# design.net
KiCad netlist of a schematic drawn in Altium Designer
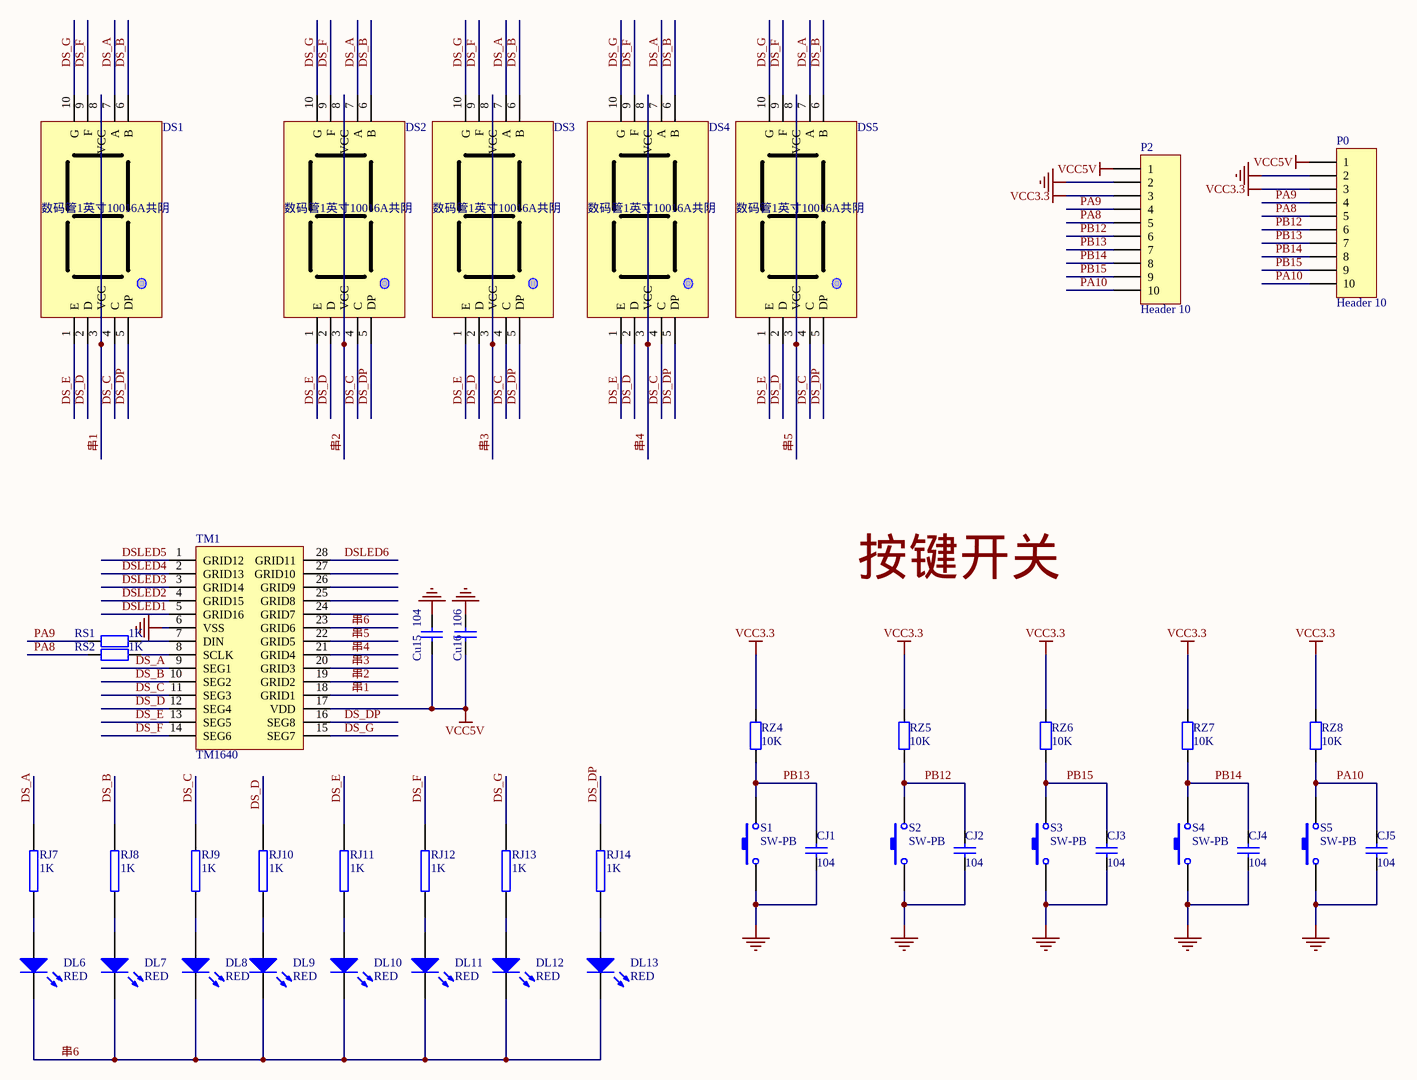
[diagram p0: 铁壳显示板.SchDoc]

(export (version "E")
  (design (tool "Eeschema 10.0.6"))
  (components
    (comp (ref "CJ1")
      (value "104")
      (footprint "0603-1")
      (description "Capacitor")
      (fields (field (name "PUBLISHER") "Altium Limited"))
      (libsource (lib "原理图库") (part "104"))
    )
    (comp (ref "CJ2")
      (value "104")
      (footprint "0603-1")
      (description "Capacitor")
      (fields (field (name "PUBLISHER") "Altium Limited"))
      (libsource (lib "原理图库") (part "104"))
    )
    (comp (ref "CJ3")
      (value "104")
      (footprint "0603-1")
      (description "Capacitor")
      (fields (field (name "PUBLISHER") "Altium Limited"))
      (libsource (lib "原理图库") (part "104"))
    )
    (comp (ref "CJ4")
      (value "104")
      (footprint "0603-1")
      (description "Capacitor")
      (fields (field (name "PUBLISHER") "Altium Limited"))
      (libsource (lib "原理图库") (part "104"))
    )
    (comp (ref "CJ5")
      (value "104")
      (footprint "0603-1")
      (description "Capacitor")
      (fields (field (name "PUBLISHER") "Altium Limited"))
      (libsource (lib "原理图库") (part "104"))
    )
    (comp (ref "Cu15")
      (value "104")
      (footprint "0603-1")
      (description "Capacitor")
      (libsource (lib "*") (part "Cap"))
    )
    (comp (ref "Cu16")
      (value "106")
      (footprint "0805")
      (description "Capacitor")
      (libsource (lib "*") (part "Cap"))
    )
    (comp (ref "DL6")
      (value "RED")
      (footprint "HDR1X2")
      (description "Typical RED GaAs LED")
      (fields (field (name "PUBLISHER") "Altium Limited"))
      (libsource (lib "原理图库") (part "LED1"))
    )
    (comp (ref "DL7")
      (value "RED")
      (footprint "HDR1X2")
      (description "Typical RED GaAs LED")
      (fields (field (name "PUBLISHER") "Altium Limited"))
      (libsource (lib "原理图库") (part "LED1"))
    )
    (comp (ref "DL8")
      (value "RED")
      (footprint "HDR1X2")
      (description "Typical RED GaAs LED")
      (fields (field (name "PUBLISHER") "Altium Limited"))
      (libsource (lib "原理图库") (part "LED1"))
    )
    (comp (ref "DL9")
      (value "RED")
      (footprint "HDR1X2")
      (description "Typical RED GaAs LED")
      (fields (field (name "PUBLISHER") "Altium Limited"))
      (libsource (lib "原理图库") (part "LED1"))
    )
    (comp (ref "DL10")
      (value "RED")
      (footprint "HDR1X2")
      (description "Typical RED GaAs LED")
      (fields (field (name "PUBLISHER") "Altium Limited"))
      (libsource (lib "原理图库") (part "LED1"))
    )
    (comp (ref "DL11")
      (value "RED")
      (footprint "HDR1X2")
      (description "Typical RED GaAs LED")
      (fields (field (name "PUBLISHER") "Altium Limited"))
      (libsource (lib "原理图库") (part "LED1"))
    )
    (comp (ref "DL12")
      (value "RED")
      (footprint "HDR1X2")
      (description "Typical RED GaAs LED")
      (fields (field (name "PUBLISHER") "Altium Limited"))
      (libsource (lib "原理图库") (part "LED1"))
    )
    (comp (ref "DL13")
      (value "RED")
      (footprint "HDR1X2")
      (description "Typical RED GaAs LED")
      (fields (field (name "PUBLISHER") "Altium Limited"))
      (libsource (lib "原理图库") (part "LED1"))
    )
    (comp (ref "DS1")
      (value "数码管1英寸10016A共阴")
      (footprint "1英寸1位数码管")
      (libsource (lib "SCH原理图库") (part "数码管1英寸"))
    )
    (comp (ref "DS2")
      (value "数码管1英寸10016A共阴")
      (footprint "1英寸1位数码管")
      (libsource (lib "SCH原理图库") (part "数码管1英寸"))
    )
    (comp (ref "DS3")
      (value "数码管1英寸10016A共阴")
      (footprint "1英寸1位数码管")
      (libsource (lib "SCH原理图库") (part "数码管1英寸"))
    )
    (comp (ref "DS4")
      (value "数码管1英寸10016A共阴")
      (footprint "1英寸1位数码管")
      (libsource (lib "SCH原理图库") (part "数码管1英寸"))
    )
    (comp (ref "DS5")
      (value "数码管1英寸10016A共阴")
      (footprint "1英寸1位数码管")
      (libsource (lib "SCH原理图库") (part "数码管1英寸"))
    )
    (comp (ref "P0")
      (value "Header 10")
      (footprint "HDR1X10")
      (description "Header, 10-Pin")
      (fields (field (name "PUBLISHER") "Altium Limited"))
      (libsource (lib "SCH原理图库") (part "Header 10"))
    )
    (comp (ref "P2")
      (value "Header 10")
      (footprint "HDR1X10")
      (description "Header, 10-Pin")
      (fields (field (name "PUBLISHER") "Altium Limited"))
      (libsource (lib "SCH原理图库") (part "Header 10"))
    )
    (comp (ref "RJ7") (value "1K") (footprint "0603-1") (libsource (lib "*") (part "RES2")))
    (comp (ref "RJ8") (value "1K") (footprint "0603-1") (libsource (lib "*") (part "RES2")))
    (comp (ref "RJ9") (value "1K") (footprint "0603-1") (libsource (lib "*") (part "RES2")))
    (comp (ref "RJ10") (value "1K") (footprint "0603-1") (libsource (lib "*") (part "RES2")))
    (comp (ref "RJ11") (value "1K") (footprint "0603-1") (libsource (lib "*") (part "RES2")))
    (comp (ref "RJ12") (value "1K") (footprint "0603-1") (libsource (lib "*") (part "RES2")))
    (comp (ref "RJ13") (value "1K") (footprint "0603-1") (libsource (lib "*") (part "RES2")))
    (comp (ref "RJ14") (value "1K") (footprint "0603-1") (libsource (lib "*") (part "RES2")))
    (comp (ref "RS1")
      (value "1K")
      (footprint "0603-1")
      (description "Resistor")
      (libsource (lib "") (part "Res2_1"))
    )
    (comp (ref "RS2")
      (value "1K")
      (footprint "0603-1")
      (description "Resistor")
      (libsource (lib "") (part "Res2_1"))
    )
    (comp (ref "RZ4")
      (value "10K")
      (footprint "0603-1")
      (description "Resistor")
      (fields (field (name "PUBLISHER") "Altium Limited"))
      (libsource (lib "Miscellaneous Devices") (part "Res2"))
    )
    (comp (ref "RZ5")
      (value "10K")
      (footprint "0603-1")
      (description "Resistor")
      (fields (field (name "PUBLISHER") "Altium Limited"))
      (libsource (lib "Miscellaneous Devices") (part "Res2"))
    )
    (comp (ref "RZ6")
      (value "10K")
      (footprint "0603-1")
      (description "Resistor")
      (fields (field (name "PUBLISHER") "Altium Limited"))
      (libsource (lib "Miscellaneous Devices") (part "Res2"))
    )
    (comp (ref "RZ7")
      (value "10K")
      (footprint "0603-1")
      (description "Resistor")
      (fields (field (name "PUBLISHER") "Altium Limited"))
      (libsource (lib "Miscellaneous Devices") (part "Res2"))
    )
    (comp (ref "RZ8")
      (value "10K")
      (footprint "0603-1")
      (description "Resistor")
      (fields (field (name "PUBLISHER") "Altium Limited"))
      (libsource (lib "Miscellaneous Devices") (part "Res2"))
    )
    (comp (ref "S1")
      (value "SW-PB")
      (footprint "SW_2 - SMT")
      (description "Switch")
      (fields (field (name "PUBLISHER") "Altium Limited"))
      (libsource (lib "SCH原理图库") (part "SW-PB"))
    )
    (comp (ref "S2")
      (value "SW-PB")
      (footprint "SW_2 - SMT")
      (description "Switch")
      (fields (field (name "PUBLISHER") "Altium Limited"))
      (libsource (lib "SCH原理图库") (part "SW-PB"))
    )
    (comp (ref "S3")
      (value "SW-PB")
      (footprint "SW_2 - SMT")
      (description "Switch")
      (fields (field (name "PUBLISHER") "Altium Limited"))
      (libsource (lib "SCH原理图库") (part "SW-PB"))
    )
    (comp (ref "S4")
      (value "SW-PB")
      (footprint "SW_2 - SMT")
      (description "Switch")
      (fields (field (name "PUBLISHER") "Altium Limited"))
      (libsource (lib "SCH原理图库") (part "SW-PB"))
    )
    (comp (ref "S5")
      (value "SW-PB")
      (footprint "SW_2 - SMT")
      (description "Switch")
      (fields (field (name "PUBLISHER") "Altium Limited"))
      (libsource (lib "SCH原理图库") (part "SW-PB"))
    )
    (comp (ref "TM1") (value "TM1640") (footprint "TM1640") (libsource (lib "SCH原理图库") (part "TM1640")))
  )
  (nets
    (net (code "1") (name "/DSLED1") (class "Default")
      (node (ref "TM1") (pin "5") (pinfunction "GRID16_5") (pintype "passive"))
    )
    (net (code "2") (name "/DSLED2") (class "Default")
      (node (ref "TM1") (pin "4") (pinfunction "GRID15_4") (pintype "passive"))
    )
    (net (code "3") (name "/DSLED3") (class "Default")
      (node (ref "TM1") (pin "3") (pinfunction "GRID14_3") (pintype "passive"))
    )
    (net (code "4") (name "/DSLED4") (class "Default")
      (node (ref "TM1") (pin "2") (pinfunction "GRID13_2") (pintype "passive"))
    )
    (net (code "5") (name "/DSLED5") (class "Default")
      (node (ref "TM1") (pin "1") (pinfunction "GRID12_1") (pintype "passive"))
    )
    (net (code "6") (name "/DSLED6") (class "Default")
      (node (ref "TM1") (pin "28") (pinfunction "GRID11_28") (pintype "passive"))
    )
    (net (code "7") (name "/DS_A") (class "Default")
      (node (ref "DS1") (pin "7") (pinfunction "A_7") (pintype "passive"))
      (node (ref "DS2") (pin "7") (pinfunction "A_7") (pintype "passive"))
      (node (ref "DS3") (pin "7") (pinfunction "A_7") (pintype "passive"))
      (node (ref "DS4") (pin "7") (pinfunction "A_7") (pintype "passive"))
      (node (ref "DS5") (pin "7") (pinfunction "A_7") (pintype "passive"))
      (node (ref "RJ7") (pin "1") (pinfunction "1_1") (pintype "passive"))
      (node (ref "TM1") (pin "9") (pinfunction "SEG1_9") (pintype "passive"))
    )
    (net (code "8") (name "/DS_B") (class "Default")
      (node (ref "DS1") (pin "6") (pinfunction "B_6") (pintype "passive"))
      (node (ref "DS2") (pin "6") (pinfunction "B_6") (pintype "passive"))
      (node (ref "DS3") (pin "6") (pinfunction "B_6") (pintype "passive"))
      (node (ref "DS4") (pin "6") (pinfunction "B_6") (pintype "passive"))
      (node (ref "DS5") (pin "6") (pinfunction "B_6") (pintype "passive"))
      (node (ref "RJ8") (pin "1") (pinfunction "1_1") (pintype "passive"))
      (node (ref "TM1") (pin "10") (pinfunction "SEG2_10") (pintype "passive"))
    )
    (net (code "9") (name "/DS_C") (class "Default")
      (node (ref "DS1") (pin "4") (pinfunction "C_4") (pintype "passive"))
      (node (ref "DS2") (pin "4") (pinfunction "C_4") (pintype "passive"))
      (node (ref "DS3") (pin "4") (pinfunction "C_4") (pintype "passive"))
      (node (ref "DS4") (pin "4") (pinfunction "C_4") (pintype "passive"))
      (node (ref "DS5") (pin "4") (pinfunction "C_4") (pintype "passive"))
      (node (ref "RJ9") (pin "1") (pinfunction "1_1") (pintype "passive"))
      (node (ref "TM1") (pin "11") (pinfunction "SEG3_11") (pintype "passive"))
    )
    (net (code "10") (name "/DS_D") (class "Default")
      (node (ref "DS1") (pin "2") (pinfunction "D_2") (pintype "passive"))
      (node (ref "DS2") (pin "2") (pinfunction "D_2") (pintype "passive"))
      (node (ref "DS3") (pin "2") (pinfunction "D_2") (pintype "passive"))
      (node (ref "DS4") (pin "2") (pinfunction "D_2") (pintype "passive"))
      (node (ref "DS5") (pin "2") (pinfunction "D_2") (pintype "passive"))
      (node (ref "RJ10") (pin "1") (pinfunction "1_1") (pintype "passive"))
      (node (ref "TM1") (pin "12") (pinfunction "SEG4_12") (pintype "passive"))
    )
    (net (code "11") (name "/DS_DP") (class "Default")
      (node (ref "DS1") (pin "5") (pinfunction "DP_5") (pintype "passive"))
      (node (ref "DS2") (pin "5") (pinfunction "DP_5") (pintype "passive"))
      (node (ref "DS3") (pin "5") (pinfunction "DP_5") (pintype "passive"))
      (node (ref "DS4") (pin "5") (pinfunction "DP_5") (pintype "passive"))
      (node (ref "DS5") (pin "5") (pinfunction "DP_5") (pintype "passive"))
      (node (ref "RJ14") (pin "1") (pinfunction "1_1") (pintype "passive"))
      (node (ref "TM1") (pin "16") (pinfunction "SEG8_16") (pintype "passive"))
    )
    (net (code "12") (name "/DS_E") (class "Default")
      (node (ref "DS1") (pin "1") (pinfunction "E_1") (pintype "passive"))
      (node (ref "DS2") (pin "1") (pinfunction "E_1") (pintype "passive"))
      (node (ref "DS3") (pin "1") (pinfunction "E_1") (pintype "passive"))
      (node (ref "DS4") (pin "1") (pinfunction "E_1") (pintype "passive"))
      (node (ref "DS5") (pin "1") (pinfunction "E_1") (pintype "passive"))
      (node (ref "RJ11") (pin "1") (pinfunction "1_1") (pintype "passive"))
      (node (ref "TM1") (pin "13") (pinfunction "SEG5_13") (pintype "passive"))
    )
    (net (code "13") (name "/DS_F") (class "Default")
      (node (ref "DS1") (pin "9") (pinfunction "F_9") (pintype "passive"))
      (node (ref "DS2") (pin "9") (pinfunction "F_9") (pintype "passive"))
      (node (ref "DS3") (pin "9") (pinfunction "F_9") (pintype "passive"))
      (node (ref "DS4") (pin "9") (pinfunction "F_9") (pintype "passive"))
      (node (ref "DS5") (pin "9") (pinfunction "F_9") (pintype "passive"))
      (node (ref "RJ12") (pin "1") (pinfunction "1_1") (pintype "passive"))
      (node (ref "TM1") (pin "14") (pinfunction "SEG6_14") (pintype "passive"))
    )
    (net (code "14") (name "/DS_G") (class "Default")
      (node (ref "DS1") (pin "10") (pinfunction "G_10") (pintype "passive"))
      (node (ref "DS2") (pin "10") (pinfunction "G_10") (pintype "passive"))
      (node (ref "DS3") (pin "10") (pinfunction "G_10") (pintype "passive"))
      (node (ref "DS4") (pin "10") (pinfunction "G_10") (pintype "passive"))
      (node (ref "DS5") (pin "10") (pinfunction "G_10") (pintype "passive"))
      (node (ref "RJ13") (pin "1") (pinfunction "1_1") (pintype "passive"))
      (node (ref "TM1") (pin "15") (pinfunction "SEG7_15") (pintype "passive"))
    )
    (net (code "15") (name "/PA8") (class "Default")
      (node (ref "P0") (pin "5") (pinfunction "5_5") (pintype "passive"))
      (node (ref "P2") (pin "5") (pinfunction "5_5") (pintype "passive"))
      (node (ref "RS2") (pin "2") (pinfunction "2_2") (pintype "passive"))
    )
    (net (code "16") (name "/PA9") (class "Default")
      (node (ref "P0") (pin "4") (pinfunction "4_4") (pintype "passive"))
      (node (ref "P2") (pin "4") (pinfunction "4_4") (pintype "passive"))
      (node (ref "RS1") (pin "2") (pinfunction "2_2") (pintype "passive"))
    )
    (net (code "17") (name "/PA10") (class "Default")
      (node (ref "CJ5") (pin "2") (pinfunction "2_2") (pintype "passive"))
      (node (ref "P0") (pin "10") (pinfunction "10_10") (pintype "passive"))
      (node (ref "P2") (pin "10") (pinfunction "10_10") (pintype "passive"))
      (node (ref "RZ8") (pin "1") (pinfunction "1_1") (pintype "passive"))
      (node (ref "S5") (pin "2") (pinfunction "2_2") (pintype "passive"))
    )
    (net (code "18") (name "/PB12") (class "Default")
      (node (ref "CJ2") (pin "2") (pinfunction "2_2") (pintype "passive"))
      (node (ref "P0") (pin "6") (pinfunction "6_6") (pintype "passive"))
      (node (ref "P2") (pin "6") (pinfunction "6_6") (pintype "passive"))
      (node (ref "RZ5") (pin "1") (pinfunction "1_1") (pintype "passive"))
      (node (ref "S2") (pin "2") (pinfunction "2_2") (pintype "passive"))
    )
    (net (code "19") (name "/PB13") (class "Default")
      (node (ref "CJ1") (pin "2") (pinfunction "2_2") (pintype "passive"))
      (node (ref "P0") (pin "7") (pinfunction "7_7") (pintype "passive"))
      (node (ref "P2") (pin "7") (pinfunction "7_7") (pintype "passive"))
      (node (ref "RZ4") (pin "1") (pinfunction "1_1") (pintype "passive"))
      (node (ref "S1") (pin "2") (pinfunction "2_2") (pintype "passive"))
    )
    (net (code "20") (name "/PB14") (class "Default")
      (node (ref "CJ4") (pin "2") (pinfunction "2_2") (pintype "passive"))
      (node (ref "P0") (pin "8") (pinfunction "8_8") (pintype "passive"))
      (node (ref "P2") (pin "8") (pinfunction "8_8") (pintype "passive"))
      (node (ref "RZ7") (pin "1") (pinfunction "1_1") (pintype "passive"))
      (node (ref "S4") (pin "2") (pinfunction "2_2") (pintype "passive"))
    )
    (net (code "21") (name "/PB15") (class "Default")
      (node (ref "CJ3") (pin "2") (pinfunction "2_2") (pintype "passive"))
      (node (ref "P0") (pin "9") (pinfunction "9_9") (pintype "passive"))
      (node (ref "P2") (pin "9") (pinfunction "9_9") (pintype "passive"))
      (node (ref "RZ6") (pin "1") (pinfunction "1_1") (pintype "passive"))
      (node (ref "S3") (pin "2") (pinfunction "2_2") (pintype "passive"))
    )
    (net (code "22") (name "/串1") (class "Default")
      (node (ref "DS1") (pin "3") (pinfunction "VCC_3") (pintype "passive"))
      (node (ref "DS1") (pin "8") (pinfunction "VCC_8") (pintype "passive"))
      (node (ref "TM1") (pin "18") (pinfunction "GRID1_18") (pintype "passive"))
    )
    (net (code "23") (name "/串2") (class "Default")
      (node (ref "DS2") (pin "3") (pinfunction "VCC_3") (pintype "passive"))
      (node (ref "DS2") (pin "8") (pinfunction "VCC_8") (pintype "passive"))
      (node (ref "TM1") (pin "19") (pinfunction "GRID2_19") (pintype "passive"))
    )
    (net (code "24") (name "/串3") (class "Default")
      (node (ref "DS3") (pin "3") (pinfunction "VCC_3") (pintype "passive"))
      (node (ref "DS3") (pin "8") (pinfunction "VCC_8") (pintype "passive"))
      (node (ref "TM1") (pin "20") (pinfunction "GRID3_20") (pintype "passive"))
    )
    (net (code "25") (name "/串4") (class "Default")
      (node (ref "DS4") (pin "3") (pinfunction "VCC_3") (pintype "passive"))
      (node (ref "DS4") (pin "8") (pinfunction "VCC_8") (pintype "passive"))
      (node (ref "TM1") (pin "21") (pinfunction "GRID4_21") (pintype "passive"))
    )
    (net (code "26") (name "/串5") (class "Default")
      (node (ref "DS5") (pin "3") (pinfunction "VCC_3") (pintype "passive"))
      (node (ref "DS5") (pin "8") (pinfunction "VCC_8") (pintype "passive"))
      (node (ref "TM1") (pin "22") (pinfunction "GRID5_22") (pintype "passive"))
    )
    (net (code "27") (name "/串6") (class "Default")
      (node (ref "DL10") (pin "2") (pinfunction "K_2") (pintype "passive"))
      (node (ref "DL11") (pin "2") (pinfunction "K_2") (pintype "passive"))
      (node (ref "DL12") (pin "2") (pinfunction "K_2") (pintype "passive"))
      (node (ref "DL13") (pin "2") (pinfunction "K_2") (pintype "passive"))
      (node (ref "DL6") (pin "2") (pinfunction "K_2") (pintype "passive"))
      (node (ref "DL7") (pin "2") (pinfunction "K_2") (pintype "passive"))
      (node (ref "DL8") (pin "2") (pinfunction "K_2") (pintype "passive"))
      (node (ref "DL9") (pin "2") (pinfunction "K_2") (pintype "passive"))
      (node (ref "TM1") (pin "23") (pinfunction "GRID6_23") (pintype "passive"))
    )
    (net (code "29") (name "GND") (class "Default")
      (node (ref "CJ1") (pin "1") (pinfunction "1_1") (pintype "passive"))
      (node (ref "CJ2") (pin "1") (pinfunction "1_1") (pintype "passive"))
      (node (ref "CJ3") (pin "1") (pinfunction "1_1") (pintype "passive"))
      (node (ref "CJ4") (pin "1") (pinfunction "1_1") (pintype "passive"))
      (node (ref "CJ5") (pin "1") (pinfunction "1_1") (pintype "passive"))
      (node (ref "Cu15") (pin "1") (pinfunction "1_1") (pintype "passive"))
      (node (ref "Cu16") (pin "2") (pinfunction "2_2") (pintype "passive"))
      (node (ref "P0") (pin "2") (pinfunction "2_2") (pintype "passive"))
      (node (ref "P2") (pin "2") (pinfunction "2_2") (pintype "passive"))
      (node (ref "S1") (pin "1") (pinfunction "1_1") (pintype "passive"))
      (node (ref "S2") (pin "1") (pinfunction "1_1") (pintype "passive"))
      (node (ref "S3") (pin "1") (pinfunction "1_1") (pintype "passive"))
      (node (ref "S4") (pin "1") (pinfunction "1_1") (pintype "passive"))
      (node (ref "S5") (pin "1") (pinfunction "1_1") (pintype "passive"))
      (node (ref "TM1") (pin "6") (pinfunction "VSS_6") (pintype "passive"))
    )
    (net (code "30") (name "Net-(DL6-A)") (class "Default")
      (node (ref "DL6") (pin "1") (pinfunction "A_1") (pintype "passive"))
      (node (ref "RJ7") (pin "2") (pinfunction "2_2") (pintype "passive"))
    )
    (net (code "31") (name "Net-(DL7-A)") (class "Default")
      (node (ref "DL7") (pin "1") (pinfunction "A_1") (pintype "passive"))
      (node (ref "RJ8") (pin "2") (pinfunction "2_2") (pintype "passive"))
    )
    (net (code "32") (name "Net-(DL8-A)") (class "Default")
      (node (ref "DL8") (pin "1") (pinfunction "A_1") (pintype "passive"))
      (node (ref "RJ9") (pin "2") (pinfunction "2_2") (pintype "passive"))
    )
    (net (code "33") (name "Net-(DL9-A)") (class "Default")
      (node (ref "DL9") (pin "1") (pinfunction "A_1") (pintype "passive"))
      (node (ref "RJ10") (pin "2") (pinfunction "2_2") (pintype "passive"))
    )
    (net (code "34") (name "Net-(DL10-A)") (class "Default")
      (node (ref "DL10") (pin "1") (pinfunction "A_1") (pintype "passive"))
      (node (ref "RJ11") (pin "2") (pinfunction "2_2") (pintype "passive"))
    )
    (net (code "35") (name "Net-(DL11-A)") (class "Default")
      (node (ref "DL11") (pin "1") (pinfunction "A_1") (pintype "passive"))
      (node (ref "RJ12") (pin "2") (pinfunction "2_2") (pintype "passive"))
    )
    (net (code "36") (name "Net-(DL12-A)") (class "Default")
      (node (ref "DL12") (pin "1") (pinfunction "A_1") (pintype "passive"))
      (node (ref "RJ13") (pin "2") (pinfunction "2_2") (pintype "passive"))
    )
    (net (code "37") (name "Net-(DL13-A)") (class "Default")
      (node (ref "DL13") (pin "1") (pinfunction "A_1") (pintype "passive"))
      (node (ref "RJ14") (pin "2") (pinfunction "2_2") (pintype "passive"))
    )
    (net (code "38") (name "Net-(TM1-DIN)") (class "Default")
      (node (ref "RS1") (pin "1") (pinfunction "1_1") (pintype "passive"))
      (node (ref "TM1") (pin "7") (pinfunction "DIN_7") (pintype "passive"))
    )
    (net (code "39") (name "Net-(TM1-SCLK)") (class "Default")
      (node (ref "RS2") (pin "1") (pinfunction "1_1") (pintype "passive"))
      (node (ref "TM1") (pin "8") (pinfunction "SCLK_8") (pintype "passive"))
    )
    (net (code "40") (name "VCC3.3") (class "Default")
      (node (ref "P0") (pin "3") (pinfunction "3_3") (pintype "passive"))
      (node (ref "P2") (pin "3") (pinfunction "3_3") (pintype "passive"))
      (node (ref "RZ4") (pin "2") (pinfunction "2_2") (pintype "passive"))
      (node (ref "RZ5") (pin "2") (pinfunction "2_2") (pintype "passive"))
      (node (ref "RZ6") (pin "2") (pinfunction "2_2") (pintype "passive"))
      (node (ref "RZ7") (pin "2") (pinfunction "2_2") (pintype "passive"))
      (node (ref "RZ8") (pin "2") (pinfunction "2_2") (pintype "passive"))
    )
    (net (code "41") (name "VCC5V") (class "Default")
      (node (ref "Cu15") (pin "2") (pinfunction "2_2") (pintype "passive"))
      (node (ref "Cu16") (pin "1") (pinfunction "1_1") (pintype "passive"))
      (node (ref "P0") (pin "1") (pinfunction "1_1") (pintype "passive"))
      (node (ref "P2") (pin "1") (pinfunction "1_1") (pintype "passive"))
      (node (ref "TM1") (pin "17") (pinfunction "VDD_17") (pintype "passive"))
    )
    (net (code "42") (name "unconnected-(TM1-GRID7-Pad24)") (class "Default")
      (node (ref "TM1") (pin "24") (pinfunction "GRID7_24") (pintype "passive"))
    )
    (net (code "43") (name "unconnected-(TM1-GRID8-Pad25)") (class "Default")
      (node (ref "TM1") (pin "25") (pinfunction "GRID8_25") (pintype "passive"))
    )
    (net (code "44") (name "unconnected-(TM1-GRID9-Pad26)") (class "Default")
      (node (ref "TM1") (pin "26") (pinfunction "GRID9_26") (pintype "passive"))
    )
    (net (code "45") (name "unconnected-(TM1-GRID10-Pad27)") (class "Default")
      (node (ref "TM1") (pin "27") (pinfunction "GRID10_27") (pintype "passive"))
    )
  )
)
